# AUX_POWER_5V.net
KiCad netlist of a schematic drawn in Altium Designer
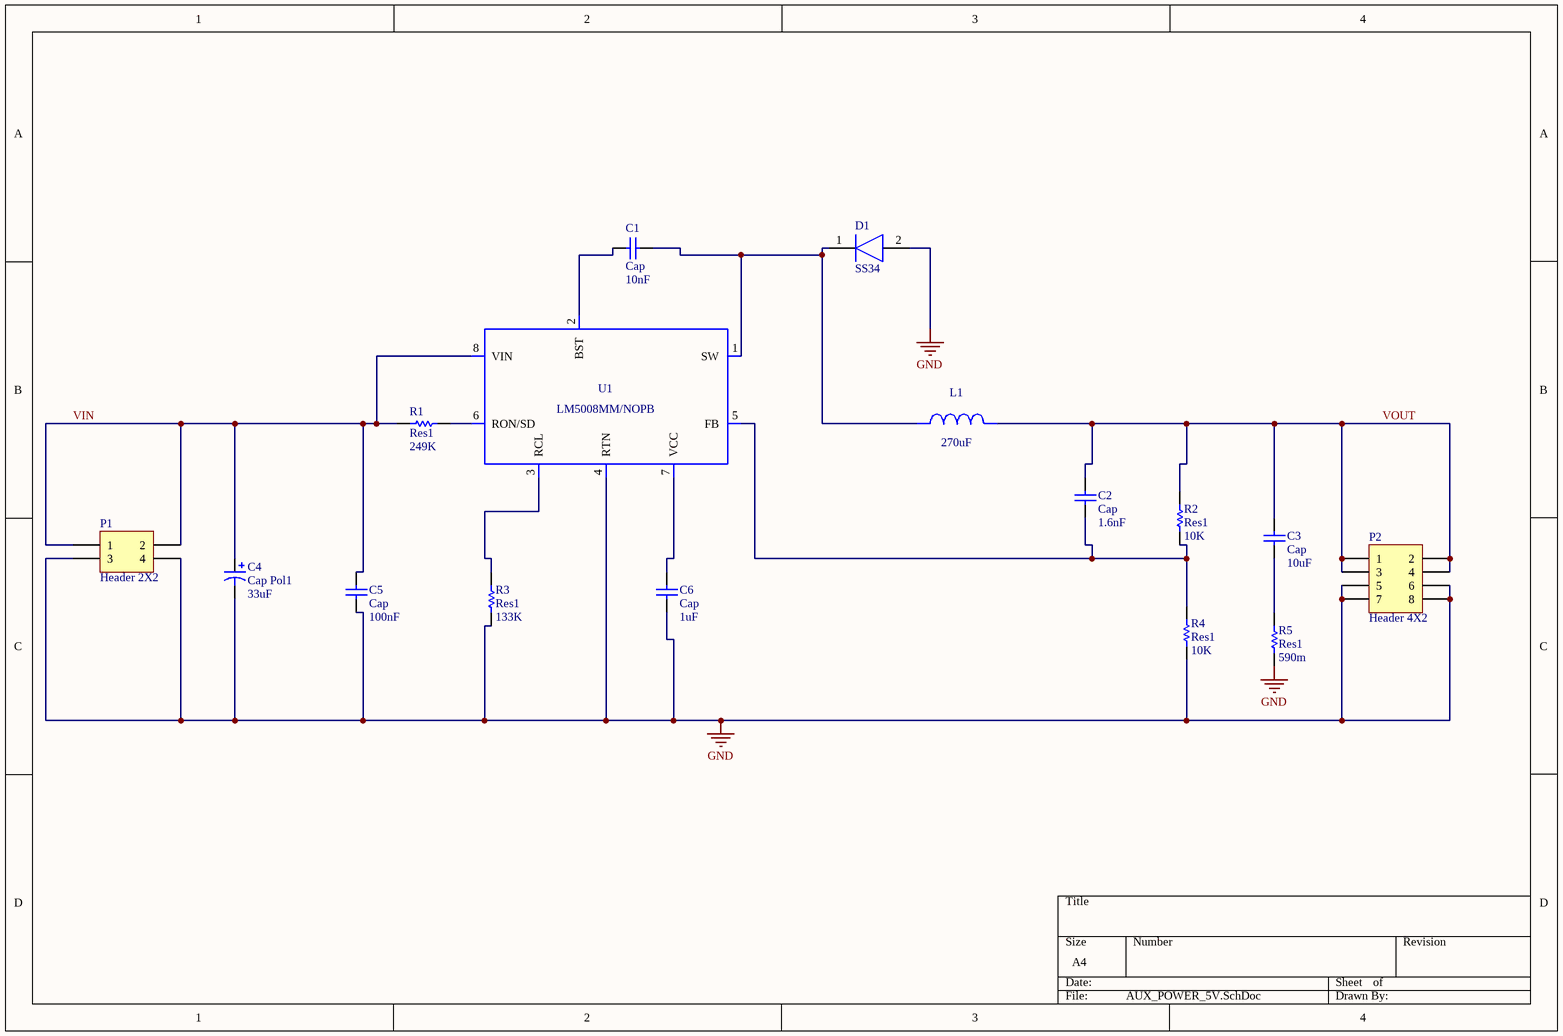
[diagram p0: AUX_POWER_5V.SchDoc]

(export (version "E")
  (design (tool "Eeschema 10.0.6"))
  (components
    (comp (ref "C1")
      (value "Cap")
      (footprint "C0805")
      (description "Capacitor")
      (fields (field (name "ALTIUM_VALUE") "10nF") (field (name "PUBLISHER") "Altium Limited"))
      (libsource (lib "Miscellaneous Devices") (part "Cap"))
    )
    (comp (ref "C2")
      (value "Cap")
      (footprint "C0805")
      (description "Capacitor")
      (fields (field (name "ALTIUM_VALUE") "1.6nF") (field (name "PUBLISHER") "Altium Limited"))
      (libsource (lib "Miscellaneous Devices") (part "Cap"))
    )
    (comp (ref "C3")
      (value "Cap")
      (footprint "C0805")
      (description "Capacitor")
      (fields (field (name "ALTIUM_VALUE") "10uF") (field (name "PUBLISHER") "Altium Limited"))
      (libsource (lib "Miscellaneous Devices") (part "Cap"))
    )
    (comp (ref "C4")
      (value "Cap Pol1")
      (footprint "C1206")
      (description "Polarized Capacitor (Radial)")
      (fields (field (name "ALTIUM_VALUE") "33uF") (field (name "PUBLISHER") "Altium Limited"))
      (libsource (lib "Miscellaneous Devices") (part "Cap Pol1"))
    )
    (comp (ref "C5")
      (value "Cap")
      (footprint "C0805")
      (description "Capacitor")
      (fields (field (name "ALTIUM_VALUE") "100nF") (field (name "PUBLISHER") "Altium Limited"))
      (libsource (lib "Miscellaneous Devices") (part "Cap"))
    )
    (comp (ref "C6")
      (value "Cap")
      (footprint "C0805")
      (description "Capacitor")
      (fields (field (name "ALTIUM_VALUE") "1uF") (field (name "PUBLISHER") "Altium Limited"))
      (libsource (lib "Miscellaneous Devices") (part "Cap"))
    )
    (comp (ref "D1")
      (value "SS34")
      (footprint "DIOM5026X262N")
      (description "Diode")
      (fields (field (name "MOUSER PART NUMBER") "512-SS34"))
      (libsource (lib "*") (part "SS34"))
    )
    (comp (ref "L1")
      (value "270uF")
      (footprint "INDUCTOR")
      (description "SRU1048-331Y")
      (libsource (lib "TI WEBENCH") (part "L1"))
    )
    (comp (ref "P1")
      (value "Header 2X2")
      (footprint "HDR2X2")
      (description "Header, 2-Pin, Dual row")
      (fields (field (name "PUBLISHER") "Altium Limited"))
      (libsource (lib "Miscellaneous Connectors") (part "Header 2X2"))
    )
    (comp (ref "P2")
      (value "Header 4X2")
      (footprint "HDR2X4")
      (description "Header, 4-Pin, Dual row")
      (fields (field (name "PUBLISHER") "Altium Limited"))
      (libsource (lib "Miscellaneous Connectors") (part "Header 4X2"))
    )
    (comp (ref "R1")
      (value "Res1")
      (footprint "1608[0603]")
      (description "Resistor")
      (fields (field (name "ALTIUM_VALUE") "249K") (field (name "PUBLISHER") "Altium Limited"))
      (libsource (lib "Miscellaneous Devices") (part "Res1"))
    )
    (comp (ref "R2")
      (value "Res1")
      (footprint "1608[0603]")
      (description "Resistor")
      (fields (field (name "ALTIUM_VALUE") "10K") (field (name "PUBLISHER") "Altium Limited"))
      (libsource (lib "Miscellaneous Devices") (part "Res1"))
    )
    (comp (ref "R3")
      (value "Res1")
      (footprint "1608[0603]")
      (description "Resistor")
      (fields (field (name "ALTIUM_VALUE") "133K") (field (name "PUBLISHER") "Altium Limited"))
      (libsource (lib "Miscellaneous Devices") (part "Res1"))
    )
    (comp (ref "R4")
      (value "Res1")
      (footprint "1608[0603]")
      (description "Resistor")
      (fields (field (name "ALTIUM_VALUE") "10K") (field (name "PUBLISHER") "Altium Limited"))
      (libsource (lib "Miscellaneous Devices") (part "Res1"))
    )
    (comp (ref "R5")
      (value "Res1")
      (footprint "1608[0603]")
      (description "Resistor")
      (fields (field (name "ALTIUM_VALUE") "590m") (field (name "PUBLISHER") "Altium Limited"))
      (libsource (lib "Miscellaneous Devices") (part "Res1"))
    )
    (comp (ref "U1")
      (value "LM5008MM/NOPB")
      (footprint "SOP65P490X110-8N")
      (fields (field (name "PACKAGEREFERENCE") "LM5008MM/NOPB"))
      (libsource (lib "TI WEBENCH") (part "U1"))
    )
  )
  (nets
    (net (code "1") (name "/VIN") (class "Default")
      (node (ref "C4") (pin "1") (pinfunction "1_1") (pintype "passive"))
      (node (ref "C5") (pin "2") (pinfunction "2_2") (pintype "passive"))
      (node (ref "P1") (pin "1") (pinfunction "1_1") (pintype "passive"))
      (node (ref "P1") (pin "2") (pinfunction "2_2") (pintype "passive"))
      (node (ref "R1") (pin "1") (pinfunction "1_1") (pintype "passive"))
      (node (ref "U1") (pin "8") (pinfunction "VIN_8") (pintype "passive"))
    )
    (net (code "2") (name "/VOUT") (class "Default")
      (node (ref "C2") (pin "2") (pinfunction "2_2") (pintype "passive"))
      (node (ref "C3") (pin "2") (pinfunction "2_2") (pintype "passive"))
      (node (ref "L1") (pin "2") (pinfunction "2_2") (pintype "passive"))
      (node (ref "P2") (pin "1") (pinfunction "1_1") (pintype "passive"))
      (node (ref "P2") (pin "2") (pinfunction "2_2") (pintype "passive"))
      (node (ref "P2") (pin "3") (pinfunction "3_3") (pintype "passive"))
      (node (ref "P2") (pin "4") (pinfunction "4_4") (pintype "passive"))
      (node (ref "R2") (pin "2") (pinfunction "2_2") (pintype "passive"))
    )
    (net (code "3") (name "GND") (class "Default")
      (node (ref "C4") (pin "2") (pinfunction "2_2") (pintype "passive"))
      (node (ref "C5") (pin "1") (pinfunction "1_1") (pintype "passive"))
      (node (ref "C6") (pin "1") (pinfunction "1_1") (pintype "passive"))
      (node (ref "D1") (pin "2") (pinfunction "A_2") (pintype "passive"))
      (node (ref "P1") (pin "3") (pinfunction "3_3") (pintype "passive"))
      (node (ref "P1") (pin "4") (pinfunction "4_4") (pintype "passive"))
      (node (ref "P2") (pin "5") (pinfunction "5_5") (pintype "passive"))
      (node (ref "P2") (pin "6") (pinfunction "6_6") (pintype "passive"))
      (node (ref "P2") (pin "7") (pinfunction "7_7") (pintype "passive"))
      (node (ref "P2") (pin "8") (pinfunction "8_8") (pintype "passive"))
      (node (ref "R3") (pin "1") (pinfunction "1_1") (pintype "passive"))
      (node (ref "R4") (pin "1") (pinfunction "1_1") (pintype "passive"))
      (node (ref "R5") (pin "1") (pinfunction "1_1") (pintype "passive"))
      (node (ref "U1") (pin "4") (pinfunction "RTN_4") (pintype "passive"))
    )
    (net (code "4") (name "Net-(C3-Pad1)") (class "Default")
      (node (ref "C3") (pin "1") (pinfunction "1_1") (pintype "passive"))
      (node (ref "R5") (pin "2") (pinfunction "2_2") (pintype "passive"))
    )
    (net (code "5") (name "Net-(D1-K)") (class "Default")
      (node (ref "C1") (pin "1") (pinfunction "1_1") (pintype "passive"))
      (node (ref "D1") (pin "1") (pinfunction "K_1") (pintype "passive"))
      (node (ref "L1") (pin "1") (pinfunction "1_1") (pintype "passive"))
      (node (ref "U1") (pin "1") (pinfunction "SW_1") (pintype "passive"))
    )
    (net (code "6") (name "Net-(U1-BST)") (class "Default")
      (node (ref "C1") (pin "2") (pinfunction "2_2") (pintype "passive"))
      (node (ref "U1") (pin "2") (pinfunction "BST_2") (pintype "passive"))
    )
    (net (code "7") (name "Net-(U1-FB)") (class "Default")
      (node (ref "C2") (pin "1") (pinfunction "1_1") (pintype "passive"))
      (node (ref "R2") (pin "1") (pinfunction "1_1") (pintype "passive"))
      (node (ref "R4") (pin "2") (pinfunction "2_2") (pintype "passive"))
      (node (ref "U1") (pin "5") (pinfunction "FB_5") (pintype "passive"))
    )
    (net (code "8") (name "Net-(U1-RCL)") (class "Default")
      (node (ref "R3") (pin "2") (pinfunction "2_2") (pintype "passive"))
      (node (ref "U1") (pin "3") (pinfunction "RCL_3") (pintype "passive"))
    )
    (net (code "9") (name "Net-(U1-RON{slash}SD)") (class "Default")
      (node (ref "R1") (pin "2") (pinfunction "2_2") (pintype "passive"))
      (node (ref "U1") (pin "6") (pinfunction "RON/SD_6") (pintype "passive"))
    )
    (net (code "10") (name "Net-(U1-VCC)") (class "Default")
      (node (ref "C6") (pin "2") (pinfunction "2_2") (pintype "passive"))
      (node (ref "U1") (pin "7") (pinfunction "VCC_7") (pintype "passive"))
    )
  )
)
